# SYS_PWR_ADC.net
KiCad netlist of a schematic drawn in Altium Designer
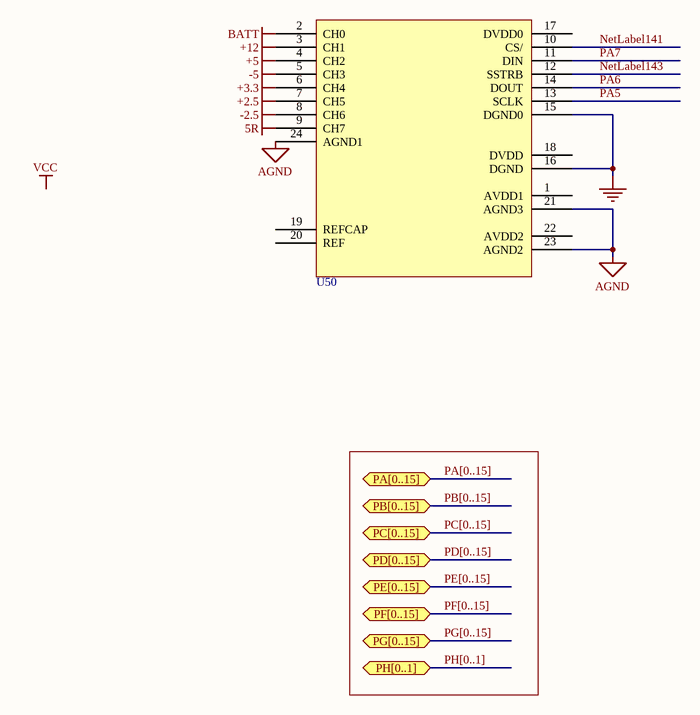
[diagram p0: SYS_PWR_ADC.SchDoc]

(export (version "E")
  (design (tool "Eeschema 10.0.6"))
  (components
    (comp (ref "U50")
      (value "MAX1300")
      (footprint "MAX1300")
      (libsource (lib "ZLS_Schematic_lib") (part "MAX1300"))
    )
  )
  (nets
    (net (code "112") (name "+2.5") (class "Default")
      (node (ref "U50") (pin "7") (pinfunction "CH5_7") (pintype "passive"))
    )
    (net (code "113") (name "+3.3") (class "Default")
      (node (ref "U50") (pin "6") (pinfunction "CH4_6") (pintype "passive"))
    )
    (net (code "114") (name "+5") (class "Default")
      (node (ref "U50") (pin "4") (pinfunction "CH2_4") (pintype "passive"))
    )
    (net (code "115") (name "+12") (class "Default")
      (node (ref "U50") (pin "3") (pinfunction "CH1_3") (pintype "passive"))
    )
    (net (code "116") (name "-2.5") (class "Default")
      (node (ref "U50") (pin "8") (pinfunction "CH6_8") (pintype "passive"))
    )
    (net (code "117") (name "-5") (class "Default")
      (node (ref "U50") (pin "5") (pinfunction "CH3_5") (pintype "passive"))
    )
    (net (code "118") (name "/NetLabel141") (class "Default")
      (node (ref "U50") (pin "10") (pinfunction "CS/_10") (pintype "passive"))
    )
    (net (code "119") (name "/NetLabel143") (class "Default")
      (node (ref "U50") (pin "12") (pinfunction "SSTRB_12") (pintype "passive"))
    )
    (net (code "120") (name "/PA5") (class "Default")
      (node (ref "U50") (pin "13") (pinfunction "SCLK_13") (pintype "passive"))
    )
    (net (code "121") (name "/PA6") (class "Default")
      (node (ref "U50") (pin "14") (pinfunction "DOUT_14") (pintype "passive"))
    )
    (net (code "122") (name "/PA7") (class "Default")
      (node (ref "U50") (pin "11") (pinfunction "DIN_11") (pintype "passive"))
    )
    (net (code "131") (name "5R") (class "Default")
      (node (ref "U50") (pin "9") (pinfunction "CH7_9") (pintype "passive"))
    )
    (net (code "132") (name "AGND") (class "Default")
      (node (ref "U50") (pin "21") (pinfunction "AGND3_21") (pintype "passive"))
      (node (ref "U50") (pin "23") (pinfunction "AGND2_23") (pintype "passive"))
      (node (ref "U50") (pin "24") (pinfunction "AGND1_24") (pintype "passive"))
    )
    (net (code "133") (name "BATT") (class "Default")
      (node (ref "U50") (pin "2") (pinfunction "CH0_2") (pintype "passive"))
    )
    (net (code "134") (name "GND") (class "Default")
      (node (ref "U50") (pin "15") (pinfunction "DGND0_15") (pintype "passive"))
      (node (ref "U50") (pin "16") (pinfunction "DGND_16") (pintype "passive"))
    )
    (net (code "136") (name "unconnected-(U50-AVDD1-Pad1)") (class "Default")
      (node (ref "U50") (pin "1") (pinfunction "AVDD1_1") (pintype "passive"))
    )
    (net (code "137") (name "unconnected-(U50-AVDD2-Pad22)") (class "Default")
      (node (ref "U50") (pin "22") (pinfunction "AVDD2_22") (pintype "passive"))
    )
    (net (code "138") (name "unconnected-(U50-DVDD-Pad18)") (class "Default")
      (node (ref "U50") (pin "18") (pinfunction "DVDD_18") (pintype "passive"))
    )
    (net (code "139") (name "unconnected-(U50-DVDD0-Pad17)") (class "Default")
      (node (ref "U50") (pin "17") (pinfunction "DVDD0_17") (pintype "passive"))
    )
    (net (code "140") (name "unconnected-(U50-REF-Pad20)") (class "Default")
      (node (ref "U50") (pin "20") (pinfunction "REF_20") (pintype "passive"))
    )
    (net (code "141") (name "unconnected-(U50-REFCAP-Pad19)") (class "Default")
      (node (ref "U50") (pin "19") (pinfunction "REFCAP_19") (pintype "passive"))
    )
  )
)
